# SOT23-3-SOT23-6.net
KiCad netlist of a schematic drawn in EAGLE
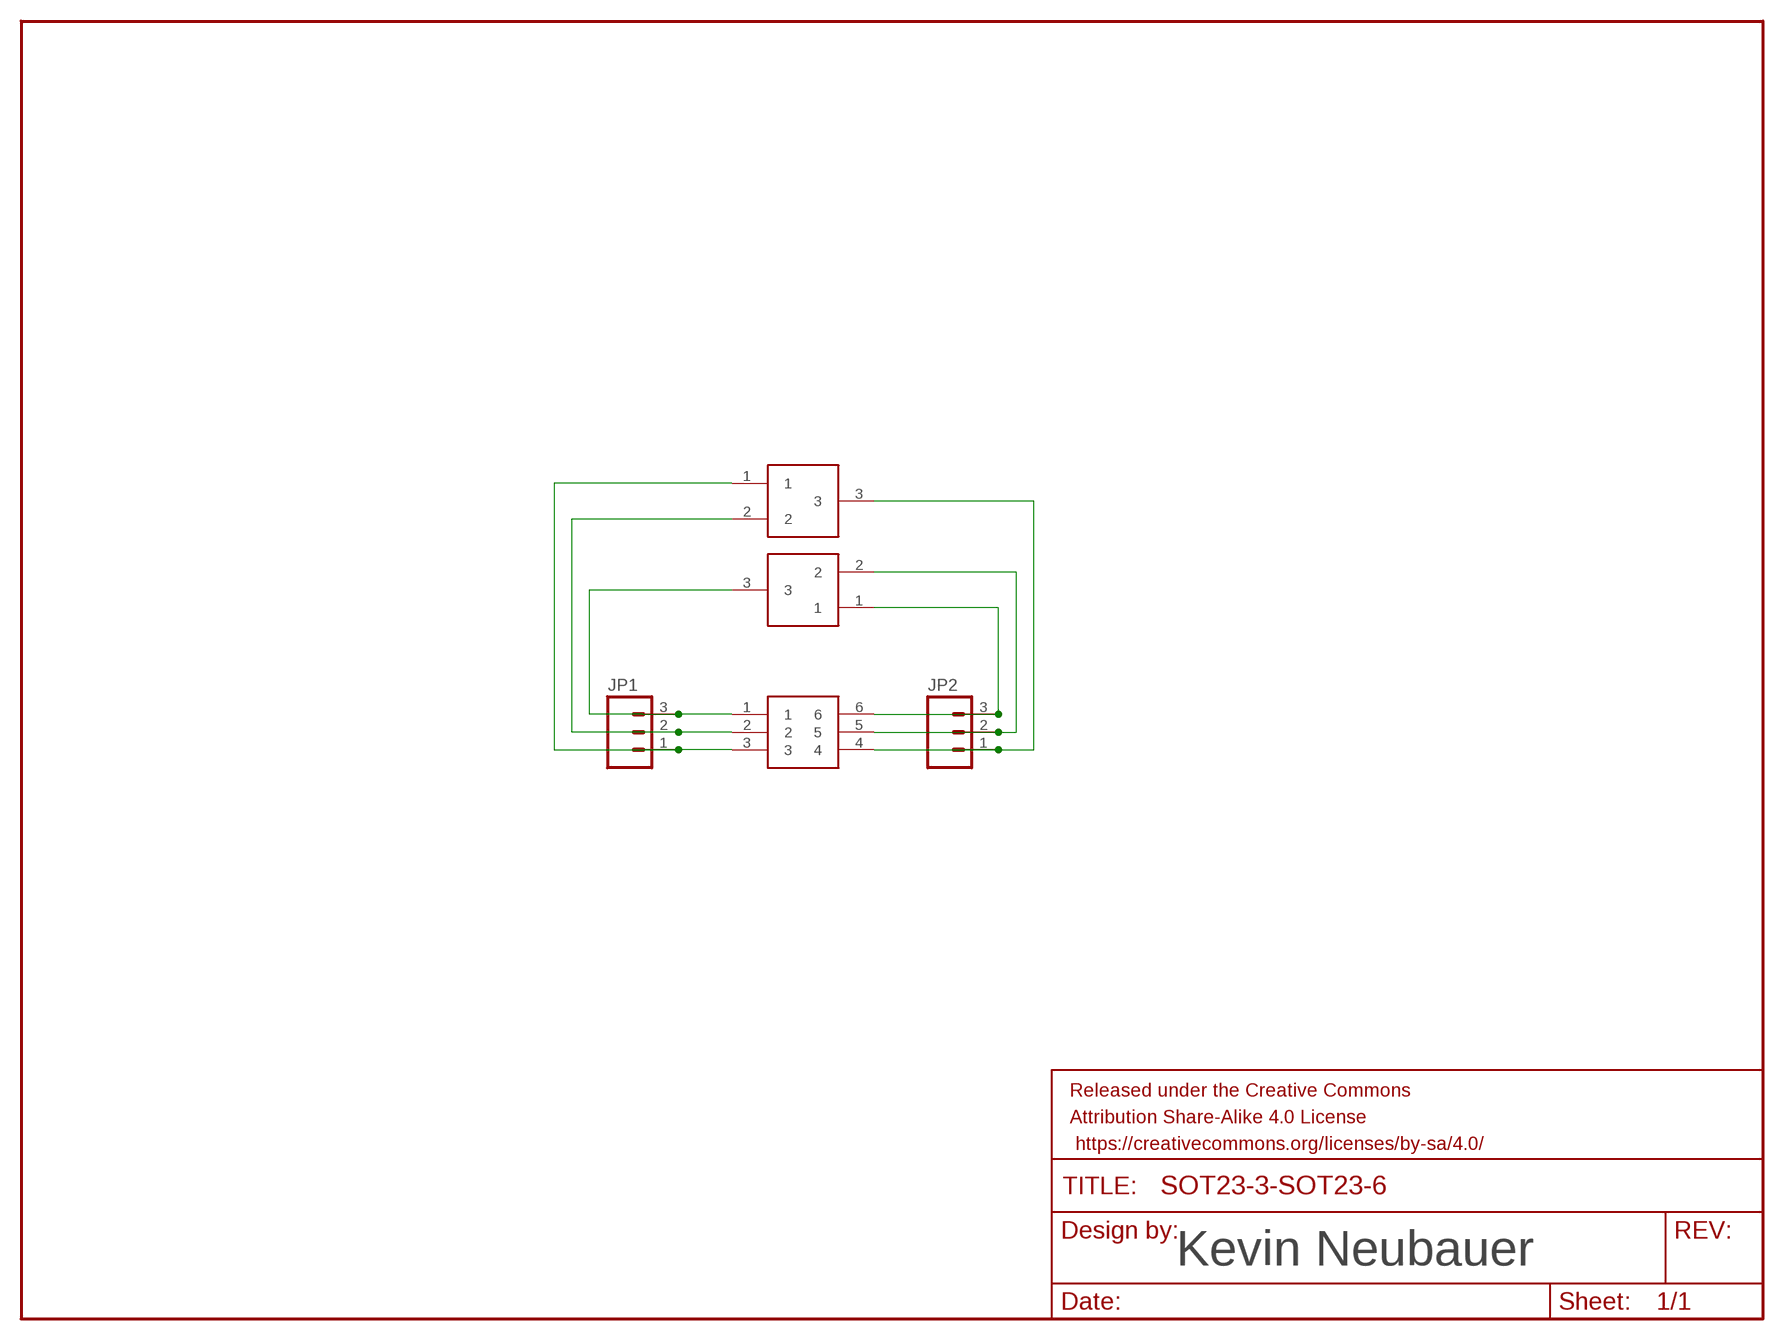
[diagram p0: schematic, sheet 1]

(export (version "E")
  (design (tool "Eeschema 10.0.6"))
  (components
    (comp (ref "FRAME1")
      (value "FRAME-LETTER")
      (footprint "eagle-import:CREATIVE_COMMONS")
      (libsource (lib "eagle-import") (part "FRAME-LETTER"))
    )
    (comp (ref "JP1")
      (value "M03PTH")
      (footprint "eagle-import:1X03")
      (libsource (lib "eagle-import") (part "M03PTH"))
    )
    (comp (ref "JP2")
      (value "M03PTH")
      (footprint "eagle-import:1X03")
      (libsource (lib "eagle-import") (part "M03PTH"))
    )
    (comp (ref "U$3")
      (value "SOT23-3")
      (footprint "eagle-import:SOT23-3")
      (libsource (lib "eagle-import") (part "SOT23-3"))
    )
    (comp (ref "U$4")
      (value "SOT23-3")
      (footprint "eagle-import:SOT23-3")
      (libsource (lib "eagle-import") (part "SOT23-3"))
    )
    (comp (ref "U$5")
      (value "SOT23-6")
      (footprint "eagle-import:SOT23-6")
      (libsource (lib "eagle-import") (part "SOT23-6"))
    )
  )
  (nets
    (net (code "1") (name "Net-(JP1-Pad1)") (class "Default")
      (node (ref "JP1") (pin "1") (pinfunction "1_1") (pintype "passive"))
      (node (ref "U$3") (pin "1") (pinfunction "1_1") (pintype "bidirectional"))
      (node (ref "U$5") (pin "3") (pinfunction "3_3") (pintype "bidirectional"))
    )
    (net (code "2") (name "Net-(JP1-Pad2)") (class "Default")
      (node (ref "JP1") (pin "2") (pinfunction "2_2") (pintype "passive"))
      (node (ref "U$3") (pin "2") (pinfunction "2_2") (pintype "bidirectional"))
      (node (ref "U$5") (pin "2") (pinfunction "2_2") (pintype "bidirectional"))
    )
    (net (code "3") (name "Net-(JP1-Pad3)") (class "Default")
      (node (ref "JP1") (pin "3") (pinfunction "3_3") (pintype "passive"))
      (node (ref "U$4") (pin "3") (pinfunction "3_3") (pintype "bidirectional"))
      (node (ref "U$5") (pin "1") (pinfunction "1_1") (pintype "bidirectional"))
    )
    (net (code "4") (name "Net-(JP2-Pad1)") (class "Default")
      (node (ref "JP2") (pin "1") (pinfunction "1_1") (pintype "passive"))
      (node (ref "U$3") (pin "3") (pinfunction "3_3") (pintype "bidirectional"))
      (node (ref "U$5") (pin "4") (pinfunction "4_4") (pintype "bidirectional"))
    )
    (net (code "5") (name "Net-(JP2-Pad2)") (class "Default")
      (node (ref "JP2") (pin "2") (pinfunction "2_2") (pintype "passive"))
      (node (ref "U$4") (pin "2") (pinfunction "2_2") (pintype "bidirectional"))
      (node (ref "U$5") (pin "5") (pinfunction "5_5") (pintype "bidirectional"))
    )
    (net (code "6") (name "Net-(JP2-Pad3)") (class "Default")
      (node (ref "JP2") (pin "3") (pinfunction "3_3") (pintype "passive"))
      (node (ref "U$4") (pin "1") (pinfunction "1_1") (pintype "bidirectional"))
      (node (ref "U$5") (pin "6") (pinfunction "6_6") (pintype "bidirectional"))
    )
  )
)
